# Base.net
KiCad netlist of a schematic drawn in Altium Designer
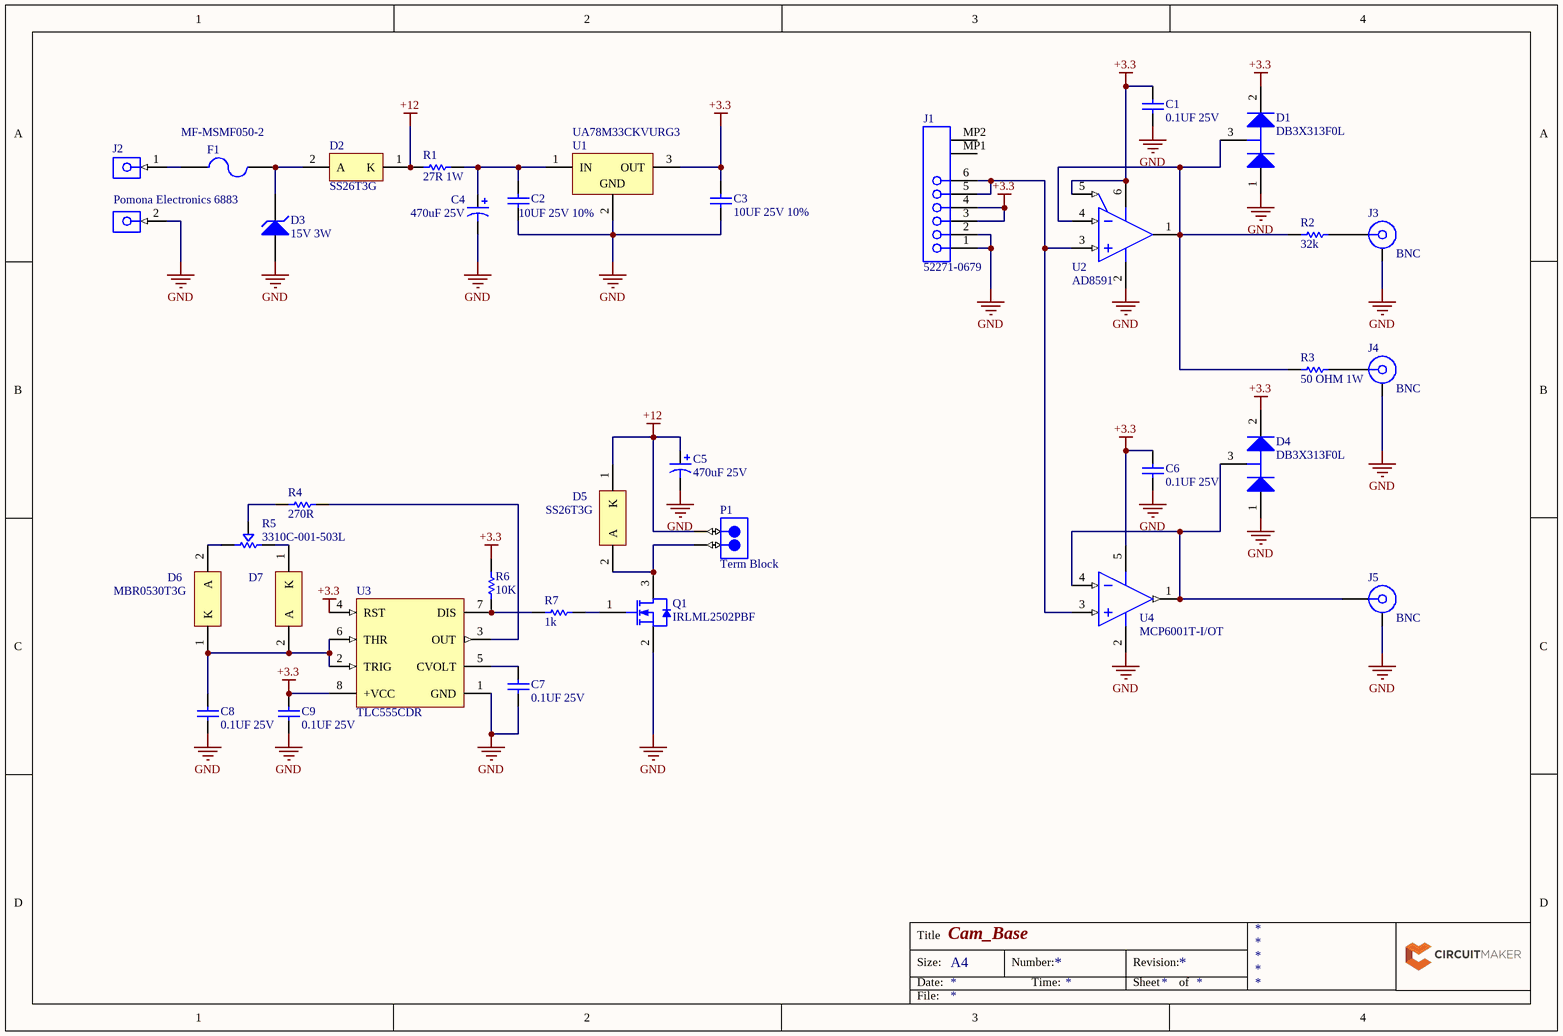
[diagram p0: Base.SchDoc]

(export (version "E")
  (design (tool "Eeschema 10.0.6"))
  (components
    (comp (ref "C1")
      (value "0.1UF 25V")
      (footprint "CAPC2013X94X50NL20T25")
      (description "CAP CER 0.1UF 25V Y5V 0805")
      (fields (field (name "MANUFACTURER PART NUMBER") "08053G104ZAT2A"))
      (libsource (lib "CommunityVault") (part "CMP-126070-1"))
    )
    (comp (ref "C2")
      (value "10UF 25V 10%")
      (footprint "PCB-121631-1")
      (description "CAP CER 10UF 25V 10% X5R 1206")
      (fields (field (name "TOLERANCE") "±10%") (field (name "MANUFACTURER PART NUMBER") "TMK316BJ106KL-T"))
      (libsource (lib "CommunityVault") (part "CMP-121631-1"))
    )
    (comp (ref "C3")
      (value "10UF 25V 10%")
      (footprint "PCB-121631-1")
      (description "CAP CER 10UF 25V 10% X5R 1206")
      (fields (field (name "TOLERANCE") "±10%") (field (name "MANUFACTURER PART NUMBER") "TMK316BJ106KL-T"))
      (libsource (lib "CommunityVault") (part "CMP-121631-1"))
    )
    (comp (ref "C4")
      (value "470uF 25V")
      (footprint "PCB-90356-1")
      (description "CAP ALUM 470UF 25V 20% SMD")
      (fields
        (field (name "MANUFACTURER PART NUMBER") "EMVA250ADA471MJA0G")
        (field (name "TOLERANCE") "±20%")
      )
      (libsource (lib "CommunityVault") (part "CMP-90356-1"))
    )
    (comp (ref "C5")
      (value "470uF 25V")
      (footprint "PCB-90356-1")
      (description "CAP ALUM 470UF 25V 20% SMD")
      (fields
        (field (name "MANUFACTURER PART NUMBER") "EMVA250ADA471MJA0G")
        (field (name "TOLERANCE") "±20%")
      )
      (libsource (lib "CommunityVault") (part "CMP-90356-1"))
    )
    (comp (ref "C6")
      (value "0.1UF 25V")
      (footprint "CAPC2013X94X50NL20T25")
      (description "CAP CER 0.1UF 25V Y5V 0805")
      (fields (field (name "MANUFACTURER PART NUMBER") "08053G104ZAT2A"))
      (libsource (lib "CommunityVault") (part "CMP-126070-1"))
    )
    (comp (ref "C7")
      (value "0.1UF 25V")
      (footprint "CAPC2013X94X50NL20T25")
      (description "CAP CER 0.1UF 25V Y5V 0805")
      (fields (field (name "MANUFACTURER PART NUMBER") "08053G104ZAT2A"))
      (libsource (lib "CommunityVault") (part "CMP-126070-1"))
    )
    (comp (ref "C8")
      (value "0.1UF 25V")
      (footprint "CAPC2013X94X50NL20T25")
      (description "CAP CER 0.1UF 25V Y5V 0805")
      (fields (field (name "MANUFACTURER PART NUMBER") "08053G104ZAT2A"))
      (libsource (lib "CommunityVault") (part "CMP-126070-1"))
    )
    (comp (ref "C9")
      (value "0.1UF 25V")
      (footprint "CAPC2013X94X50NL20T25")
      (description "CAP CER 0.1UF 25V Y5V 0805")
      (fields (field (name "MANUFACTURER PART NUMBER") "08053G104ZAT2A"))
      (libsource (lib "CommunityVault") (part "CMP-126070-1"))
    )
    (comp (ref "D1")
      (value "DB3X313F0L")
      (footprint "PCB-810955-2")
      (description "DIODE SCHOTTKY 30V 200MA")
      (libsource (lib "CommunityVault") (part "CMP-810955-1"))
    )
    (comp (ref "D2")
      (value "SS26T3G")
      (footprint "ONSC-SMB-2-403A-03_V")
      (description "Schottky Power Rectifier, 2-Pin SMB, Pb-Free, Tape and Reel")
      (libsource (lib "") (part "CMP-4964409-1_1"))
    )
    (comp (ref "D3")
      (value "15V 3W")
      (footprint "PCB-19354311-1")
      (description "DIODE ZENER 15V 3W SMB")
      (fields (field (name "MANUFACTURER PART NUMBER") "1SMB5929BT3G"))
      (libsource (lib "CommunityVault") (part "CMP-19354311-7"))
    )
    (comp (ref "D4")
      (value "DB3X313F0L")
      (footprint "PCB-810955-2")
      (description "DIODE SCHOTTKY 30V 200MA")
      (libsource (lib "CommunityVault") (part "CMP-810955-1"))
    )
    (comp (ref "D5")
      (value "SS26T3G")
      (footprint "ONSC-SMB-2-403A-03_V")
      (description "Schottky Power Rectifier, 2-Pin SMB, Pb-Free, Tape and Reel")
      (libsource (lib "CommunityVault") (part "CMP-4964409-1"))
    )
    (comp (ref "D6")
      (value "MBR0530T3G")
      (footprint "ONSC-SOD-123-2-425-04_V")
      (description "Schottky Power Rectifier, 2-Pin SOD-123, Pb-Free, Tape and Reel")
      (libsource (lib "") (part "CMP-822415-1_1"))
    )
    (comp (ref "D7")
      (value "MBR0530T3G")
      (footprint "ONSC-SOD-123-2-425-04_V")
      (description "Schottky Power Rectifier, 2-Pin SOD-123, Pb-Free, Tape and Reel")
      (libsource (lib "CommunityVault") (part "CMP-822415-1"))
    )
    (comp (ref "F1")
      (value "MF-MSMF050-2")
      (footprint "L1812")
      (description "PTC RESETTABLE .50A 15V 1812")
      (fields (field (name "MANUFACTURER") "Bourns"))
      (libsource (lib "CommunityVault") (part "CMP-277735-3"))
    )
    (comp (ref "J1")
      (value "52271-0679")
      (footprint "MOLX-52271-0679")
      (libsource (lib "CommunityVault") (part "CMP-605082-2"))
    )
    (comp (ref "J2")
      (value "Pomona Electronics 6883")
      (footprint "PCB-19368571-1")
      (description "DUAL BINDING POSTS")
      (fields (field (name "MANUFACTURER PART NUMBER") "6883") (field (name "MANUFACTURER") "Pomona"))
      (libsource (lib "CommunityVault") (part "CMP-19368571-1"))
    )
    (comp (ref "J3")
      (value "BNC")
      (footprint "ROS-71K101-400A5_V")
      (description "BNC5 STRAIGHT CABLE JACK")
      (fields (field (name "MANUFACTURER PART NUMBER") "BNC5-J-P-GN-ST-TH2D"))
      (libsource (lib "CommunityVault") (part "CMP-5779173-A.1"))
    )
    (comp (ref "J4")
      (value "BNC")
      (footprint "ROS-71K101-400A5_V")
      (description "BNC5 STRAIGHT CABLE JACK")
      (fields (field (name "MANUFACTURER PART NUMBER") "BNC5-J-P-GN-ST-TH2D"))
      (libsource (lib "CommunityVault") (part "CMP-5779173-A.1"))
    )
    (comp (ref "J5")
      (value "BNC")
      (footprint "ROS-71K101-400A5_V")
      (description "BNC5 STRAIGHT CABLE JACK")
      (fields (field (name "MANUFACTURER PART NUMBER") "BNC5-J-P-GN-ST-TH2D"))
      (libsource (lib "CommunityVault") (part "CMP-5779173-A.1"))
    )
    (comp (ref "P1")
      (value "Term Block")
      (footprint "PCB-751788-1")
      (description "CONN TERM BLOCK 2POS 5.08MM PCB")
      (fields
        (field (name "MANUFACTURER") "Phoenix Contact")
        (field (name "MANUFACTURER PART NUMBER") "1729128")
      )
      (libsource (lib "CommunityVault") (part "CMP-751788-14"))
    )
    (comp (ref "Q1")
      (value "IRLML2502PBF")
      (footprint "SOT-23-NB3_M")
      (description "MOSFET MOSFT 20V 4.2A 45mOhm 8nC Log Lvl")
      (fields (field (name "MANUFACTURER PART NUMBER") "IRLML2502TRPBF"))
      (libsource (lib "CommunityVault") (part "CMP-2602693-1"))
    )
    (comp (ref "R1")
      (value "27R 1W")
      (footprint "ROHM-MCR100-2_V")
      (description "RES SMD 27 OHM 5% 1W 2512")
      (fields (field (name "MANUFACTURER") "Vishay") (field (name "TOLERANCE") "5 %"))
      (libsource (lib "CommunityVault") (part "CMP-1861555-1"))
    )
    (comp (ref "R2")
      (value "32k")
      (footprint "RESC3216X60X45NL10T20")
      (description "RES SMD 332K OHM 1% 1/4W 1206")
      (fields (field (name "TOLERANCE") "1 %") (field (name "MANUFACTURER") "Vishay"))
      (libsource (lib "CommunityVault") (part "CMP-1867887-1"))
    )
    (comp (ref "R3")
      (value "50 OHM 1W")
      (footprint "PCB-1863557-1")
      (description "RES SMD 50 OHM 1% 1W 2515")
      (fields (field (name "MANUFACTURER PART NUMBER") "WSC251550R00FEA"))
      (libsource (lib "CommunityVault") (part "CMP-1863557-1"))
    )
    (comp (ref "R4")
      (value "270R")
      (footprint "PCB-1849257-1")
      (description "RESISTOR, 1206, 0.25W, 1%, 270R")
      (fields
        (field (name "MANUFACTURER PART NUMBER") "ERJ-8ENF2700V")
        (field (name "MANUFACTURER") "Panasonic")
      )
      (libsource (lib "CommunityVault") (part "CMP-1849257-1"))
    )
    (comp (ref "R5")
      (value "3310C-001-503L")
      (footprint "PCB-1209584-1")
      (description "POT 50K OHM 9MM SQ RTANG PLAST")
      (fields (field (name "TOLERANCE") "±20%"))
      (libsource (lib "CommunityVault") (part "CMP-1209584-1"))
    )
    (comp (ref "R6")
      (value "10K")
      (footprint "RESC3216X60X45ML10T20")
      (description "Thick Film Resistors - SMD 1/4watt 10Kohms 5%")
      (fields (field (name "TOLERANCE") "5 %") (field (name "MANUFACTURER PART NUMBER") "CRCW120610K0JNEB"))
      (libsource (lib "CommunityVault") (part "CMP-3656780-1"))
    )
    (comp (ref "R7")
      (value "1k")
      (footprint "RESC3216X60X45ML10T20")
      (description "Res Thick Film 1206 1K Ohm 5% 0.25W(1/4W) ±200ppm/C Molded SMD Automotive Paper T/R")
      (fields
        (field (name "MANUFACTURER") "Vishay")
        (field (name "MANUFACTURER PART NUMBER") "CRCW12061K00JNEA")
      )
      (libsource (lib "CommunityVault") (part "CMP-1858076-1"))
    )
    (comp (ref "U1")
      (value "UA78M33CKVURG3")
      (footprint "PCB-19361514-1")
      (description "TEXAS INSTRUMENTS   UA78M33CKVURG3   VOLT REG, 3.3V, TO-252")
      (fields (field (name "MANUFACTURER") "Texas Instruments"))
      (libsource (lib "CommunityVault") (part "CMP-19361514-3"))
    )
    (comp (ref "U2")
      (value "AD8591")
      (footprint "ADI-RJ-6_N")
      (fields (field (name "MANUFACTURER") "Analog Devices"))
      (libsource (lib "CommunityVault") (part "CMP-1324845-1"))
    )
    (comp (ref "U3")
      (value "TLC555CDR")
      (footprint "PCB-13603382-1")
      (description "IC, TIMER, SMD, SOIC8, 555")
      (libsource (lib "CommunityVault") (part "CMP-13603382-1"))
    )
    (comp (ref "U4")
      (value "MCP6001T-I/OT")
      (footprint "SOT-23-OT5_L")
      (description "1 MHz, Low-Power Operational Amplifier, 5-Pin SOT-23, Industrial Temperature, Tape and Reel")
      (libsource (lib "CommunityVault") (part "CMP-1319525-2"))
    )
  )
  (nets
    (net (code "1") (name "+3.3") (class "Default")
      (node (ref "C1") (pin "1") (pinfunction "1_1") (pintype "passive"))
      (node (ref "C3") (pin "2") (pinfunction "2_2") (pintype "passive"))
      (node (ref "C6") (pin "1") (pinfunction "1_1") (pintype "passive"))
      (node (ref "C9") (pin "1") (pinfunction "1_1") (pintype "passive"))
      (node (ref "D1") (pin "2") (pinfunction "K_2") (pintype "passive"))
      (node (ref "D4") (pin "2") (pinfunction "K_2") (pintype "passive"))
      (node (ref "J1") (pin "3") (pinfunction "3_3") (pintype "passive"))
      (node (ref "J1") (pin "4") (pinfunction "4_4") (pintype "passive"))
      (node (ref "R6") (pin "2") (pinfunction "2_2") (pintype "passive"))
      (node (ref "U1") (pin "3") (pinfunction "OUT_3") (pintype "power_in"))
      (node (ref "U2") (pin "5") (pinfunction "~{SD}_5") (pintype "input"))
      (node (ref "U2") (pin "6") (pinfunction "+V_6") (pintype "power_in"))
      (node (ref "U3") (pin "4") (pinfunction "RST_4") (pintype "input"))
      (node (ref "U3") (pin "8") (pinfunction "+VCC_8") (pintype "power_in"))
      (node (ref "U4") (pin "5") (pinfunction "VDD_5") (pintype "power_in"))
    )
    (net (code "2") (name "+12") (class "Default")
      (node (ref "C5") (pin "1") (pinfunction "1_1") (pintype "passive"))
      (node (ref "D2") (pin "1") (pinfunction "K_1") (pintype "passive"))
      (node (ref "D5") (pin "1") (pinfunction "K_1") (pintype "passive"))
      (node (ref "P1") (pin "1") (pinfunction "1_1") (pintype "bidirectional"))
      (node (ref "R1") (pin "1") (pinfunction "1_1") (pintype "passive"))
    )
    (net (code "3") (name "GND") (class "Default")
      (node (ref "C1") (pin "2") (pinfunction "2_2") (pintype "passive"))
      (node (ref "C2") (pin "1") (pinfunction "1_1") (pintype "passive"))
      (node (ref "C3") (pin "1") (pinfunction "1_1") (pintype "passive"))
      (node (ref "C4") (pin "2") (pinfunction "2_2") (pintype "passive"))
      (node (ref "C5") (pin "2") (pinfunction "2_2") (pintype "passive"))
      (node (ref "C6") (pin "2") (pinfunction "2_2") (pintype "passive"))
      (node (ref "C7") (pin "2") (pinfunction "2_2") (pintype "passive"))
      (node (ref "C8") (pin "2") (pinfunction "2_2") (pintype "passive"))
      (node (ref "C9") (pin "2") (pinfunction "2_2") (pintype "passive"))
      (node (ref "D1") (pin "1") (pinfunction "A_1") (pintype "passive"))
      (node (ref "D3") (pin "1") (pinfunction "A_1") (pintype "passive"))
      (node (ref "D4") (pin "1") (pinfunction "A_1") (pintype "passive"))
      (node (ref "J1") (pin "1") (pinfunction "1_1") (pintype "passive"))
      (node (ref "J1") (pin "2") (pinfunction "2_2") (pintype "passive"))
      (node (ref "J2") (pin "2") (pinfunction "-_2") (pintype "input"))
      (node (ref "J3") (pin "MH") (pinfunction "MH_MH") (pintype "passive"))
      (node (ref "J4") (pin "MH") (pinfunction "MH_MH") (pintype "passive"))
      (node (ref "J5") (pin "MH") (pinfunction "MH_MH") (pintype "passive"))
      (node (ref "Q1") (pin "2") (pinfunction "S_2") (pintype "passive"))
      (node (ref "U1") (pin "2") (pinfunction "GND_2") (pintype "power_in"))
      (node (ref "U2") (pin "2") (pinfunction "-V_2") (pintype "power_in"))
      (node (ref "U3") (pin "1") (pinfunction "GND_1") (pintype "power_in"))
      (node (ref "U4") (pin "2") (pinfunction "VSS_2") (pintype "power_in"))
    )
    (net (code "4") (name "Net-(D1-K{slash}A)") (class "Default")
      (node (ref "D1") (pin "3") (pinfunction "K/A_3") (pintype "passive"))
      (node (ref "R2") (pin "1") (pinfunction "1_1") (pintype "passive"))
      (node (ref "R3") (pin "1") (pinfunction "1_1") (pintype "passive"))
      (node (ref "U2") (pin "1") (pinfunction "OUT_A_1") (pintype "tri_state"))
      (node (ref "U2") (pin "4") (pinfunction "-IN_A_4") (pintype "input"))
    )
    (net (code "5") (name "Net-(D2-A)") (class "Default")
      (node (ref "D2") (pin "2") (pinfunction "A_2") (pintype "passive"))
      (node (ref "D3") (pin "2") (pinfunction "K_2") (pintype "passive"))
      (node (ref "F1") (pin "2") (pinfunction "2_2") (pintype "passive"))
    )
    (net (code "6") (name "Net-(D4-K{slash}A)") (class "Default")
      (node (ref "D4") (pin "3") (pinfunction "K/A_3") (pintype "passive"))
      (node (ref "J5") (pin "1") (pinfunction "1_1") (pintype "passive"))
      (node (ref "U4") (pin "1") (pinfunction "VOUT_1") (pintype "output"))
      (node (ref "U4") (pin "4") (pinfunction "VIN-_4") (pintype "input"))
    )
    (net (code "7") (name "Net-(D5-A)") (class "Default")
      (node (ref "D5") (pin "2") (pinfunction "A_2") (pintype "passive"))
      (node (ref "P1") (pin "2") (pinfunction "2_2") (pintype "bidirectional"))
      (node (ref "Q1") (pin "3") (pinfunction "D_3") (pintype "passive"))
    )
    (net (code "8") (name "Net-(D6-A)") (class "Default")
      (node (ref "D6") (pin "2") (pinfunction "A_2") (pintype "passive"))
      (node (ref "R5") (pin "1") (pinfunction "1_1") (pintype "passive"))
    )
    (net (code "9") (name "Net-(D6-K)") (class "Default")
      (node (ref "C8") (pin "1") (pinfunction "1_1") (pintype "passive"))
      (node (ref "D6") (pin "1") (pinfunction "K_1") (pintype "passive"))
      (node (ref "D7") (pin "2") (pinfunction "A_2") (pintype "passive"))
      (node (ref "U3") (pin "2") (pinfunction "TRIG_2") (pintype "input"))
      (node (ref "U3") (pin "6") (pinfunction "THR_6") (pintype "input"))
    )
    (net (code "10") (name "Net-(D7-K)") (class "Default")
      (node (ref "D7") (pin "1") (pinfunction "K_1") (pintype "passive"))
      (node (ref "R5") (pin "3") (pinfunction "3_3") (pintype "passive"))
    )
    (net (code "11") (name "Net-(J2-+)") (class "Default")
      (node (ref "F1") (pin "1") (pinfunction "1_1") (pintype "passive"))
      (node (ref "J2") (pin "1") (pinfunction "+_1") (pintype "input"))
    )
    (net (code "12") (name "Net-(J3-Pad1)") (class "Default")
      (node (ref "J3") (pin "1") (pinfunction "1_1") (pintype "passive"))
      (node (ref "R2") (pin "2") (pinfunction "2_2") (pintype "passive"))
    )
    (net (code "13") (name "Net-(J4-Pad1)") (class "Default")
      (node (ref "J4") (pin "1") (pinfunction "1_1") (pintype "passive"))
      (node (ref "R3") (pin "2") (pinfunction "2_2") (pintype "passive"))
    )
    (net (code "14") (name "Net-(Q1-G)") (class "Default")
      (node (ref "Q1") (pin "1") (pinfunction "G_1") (pintype "passive"))
      (node (ref "R7") (pin "2") (pinfunction "2_2") (pintype "passive"))
    )
    (net (code "15") (name "Net-(R4-Pad1)") (class "Default")
      (node (ref "R4") (pin "1") (pinfunction "1_1") (pintype "passive"))
      (node (ref "R5") (pin "2") (pinfunction "2_2") (pintype "passive"))
    )
    (net (code "16") (name "Net-(U1-IN)") (class "Default")
      (node (ref "C2") (pin "2") (pinfunction "2_2") (pintype "passive"))
      (node (ref "C4") (pin "1") (pinfunction "1_1") (pintype "passive"))
      (node (ref "R1") (pin "2") (pinfunction "2_2") (pintype "passive"))
      (node (ref "U1") (pin "1") (pinfunction "IN_1") (pintype "power_in"))
    )
    (net (code "17") (name "Net-(U2-+IN_A)") (class "Default")
      (node (ref "J1") (pin "5") (pinfunction "5_5") (pintype "passive"))
      (node (ref "J1") (pin "6") (pinfunction "6_6") (pintype "passive"))
      (node (ref "U2") (pin "3") (pinfunction "+IN_A_3") (pintype "input"))
      (node (ref "U4") (pin "3") (pinfunction "VIN+_3") (pintype "input"))
    )
    (net (code "18") (name "Net-(U3-CVOLT)") (class "Default")
      (node (ref "C7") (pin "1") (pinfunction "1_1") (pintype "passive"))
      (node (ref "U3") (pin "5") (pinfunction "CVOLT_5") (pintype "passive"))
    )
    (net (code "19") (name "Net-(U3-DIS)") (class "Default")
      (node (ref "R6") (pin "1") (pinfunction "1_1") (pintype "passive"))
      (node (ref "R7") (pin "1") (pinfunction "1_1") (pintype "passive"))
      (node (ref "U3") (pin "7") (pinfunction "DIS_7") (pintype "open_collector"))
    )
    (net (code "20") (name "Net-(U3-OUT)") (class "Default")
      (node (ref "R4") (pin "2") (pinfunction "2_2") (pintype "passive"))
      (node (ref "U3") (pin "3") (pinfunction "OUT_3") (pintype "output"))
    )
    (net (code "21") (name "unconnected-(J1-PadMP1)") (class "Default")
      (node (ref "J1") (pin "MP1") (pinfunction "MP1_MP1") (pintype "passive"))
    )
    (net (code "22") (name "unconnected-(J1-PadMP2)") (class "Default")
      (node (ref "J1") (pin "MP2") (pinfunction "MP2_MP2") (pintype "passive"))
    )
  )
)
